# tick-mk-1.net
KiCad netlist of a schematic drawn in EAGLE
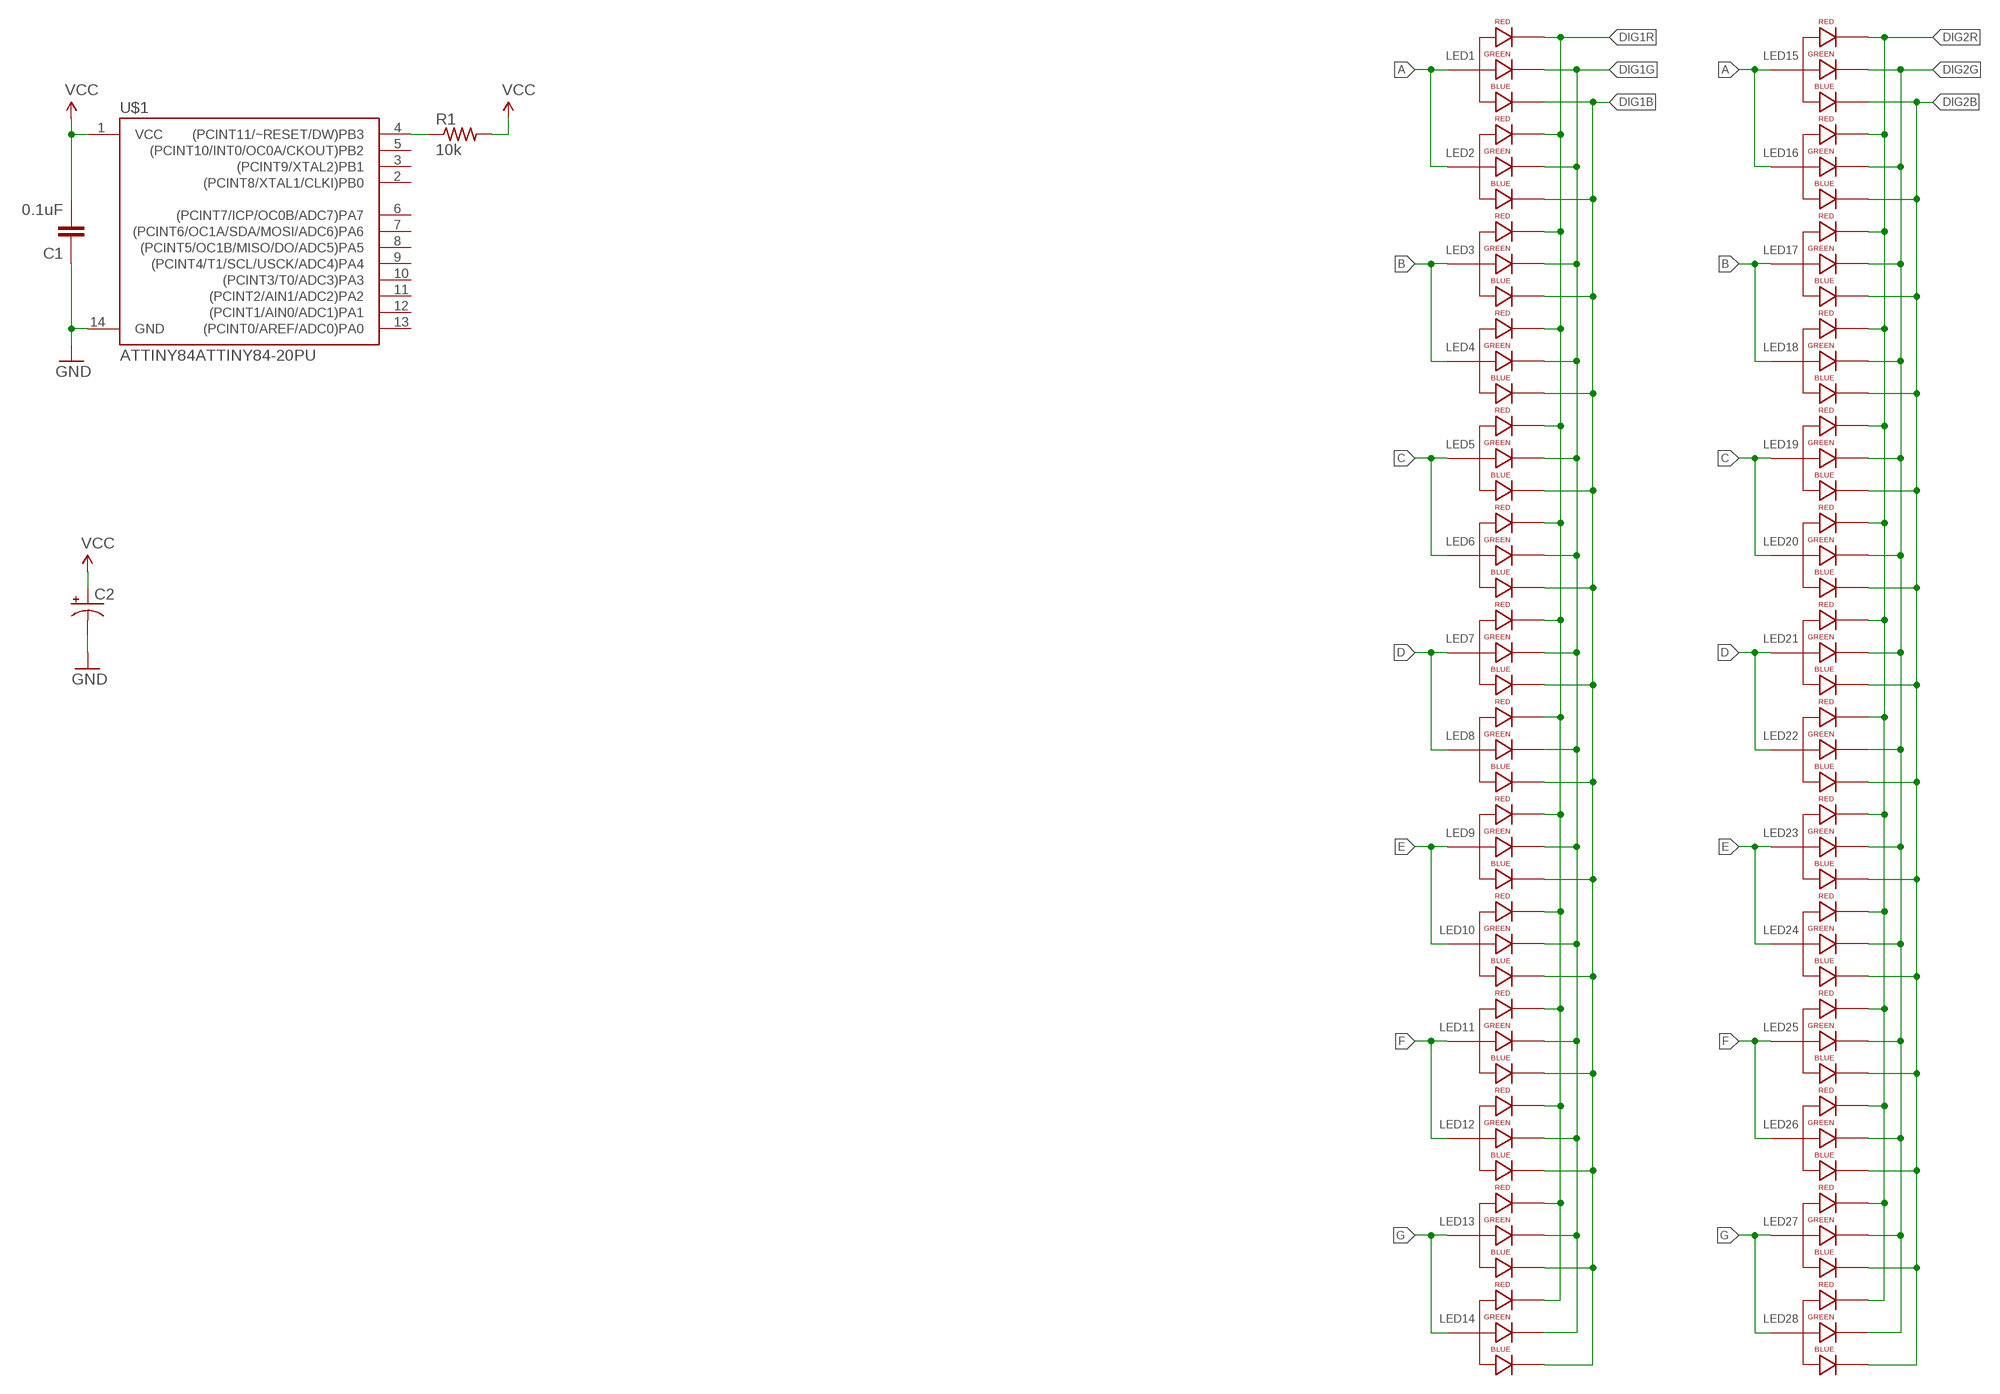
[diagram p0: schematic, sheet 1]

(export (version "E")
  (design (tool "Eeschema 10.0.6"))
  (components
    (comp (ref "C1")
      (value "0.1uF")
      (footprint "eagle-import:C025-024X044")
      (libsource (lib "eagle-import") (part "CAPACITOR-CERAMIC025-024X044"))
    )
    (comp (ref "C2")
      (value "CAPACITOR-POLARIZEDE2-5")
      (footprint "eagle-import:E2-5")
      (libsource (lib "eagle-import") (part "CAPACITOR-POLARIZEDE2-5"))
    )
    (comp (ref "LED1")
      (value "LED-RGB-CA-THRUCLEAR")
      (footprint "eagle-import:LED-RGB-THRU")
      (libsource (lib "eagle-import") (part "LED-RGB-CA-THRUCLEAR"))
    )
    (comp (ref "LED2")
      (value "LED-RGB-CA-THRUCLEAR")
      (footprint "eagle-import:LED-RGB-THRU")
      (libsource (lib "eagle-import") (part "LED-RGB-CA-THRUCLEAR"))
    )
    (comp (ref "LED3")
      (value "LED-RGB-CA-THRUCLEAR")
      (footprint "eagle-import:LED-RGB-THRU")
      (libsource (lib "eagle-import") (part "LED-RGB-CA-THRUCLEAR"))
    )
    (comp (ref "LED4")
      (value "LED-RGB-CA-THRUCLEAR")
      (footprint "eagle-import:LED-RGB-THRU")
      (libsource (lib "eagle-import") (part "LED-RGB-CA-THRUCLEAR"))
    )
    (comp (ref "LED5")
      (value "LED-RGB-CA-THRUCLEAR")
      (footprint "eagle-import:LED-RGB-THRU")
      (libsource (lib "eagle-import") (part "LED-RGB-CA-THRUCLEAR"))
    )
    (comp (ref "LED6")
      (value "LED-RGB-CA-THRUCLEAR")
      (footprint "eagle-import:LED-RGB-THRU")
      (libsource (lib "eagle-import") (part "LED-RGB-CA-THRUCLEAR"))
    )
    (comp (ref "LED7")
      (value "LED-RGB-CA-THRUCLEAR")
      (footprint "eagle-import:LED-RGB-THRU")
      (libsource (lib "eagle-import") (part "LED-RGB-CA-THRUCLEAR"))
    )
    (comp (ref "LED8")
      (value "LED-RGB-CA-THRUCLEAR")
      (footprint "eagle-import:LED-RGB-THRU")
      (libsource (lib "eagle-import") (part "LED-RGB-CA-THRUCLEAR"))
    )
    (comp (ref "LED9")
      (value "LED-RGB-CA-THRUCLEAR")
      (footprint "eagle-import:LED-RGB-THRU")
      (libsource (lib "eagle-import") (part "LED-RGB-CA-THRUCLEAR"))
    )
    (comp (ref "LED10")
      (value "LED-RGB-CA-THRUCLEAR")
      (footprint "eagle-import:LED-RGB-THRU")
      (libsource (lib "eagle-import") (part "LED-RGB-CA-THRUCLEAR"))
    )
    (comp (ref "LED11")
      (value "LED-RGB-CA-THRUCLEAR")
      (footprint "eagle-import:LED-RGB-THRU")
      (libsource (lib "eagle-import") (part "LED-RGB-CA-THRUCLEAR"))
    )
    (comp (ref "LED12")
      (value "LED-RGB-CA-THRUCLEAR")
      (footprint "eagle-import:LED-RGB-THRU")
      (libsource (lib "eagle-import") (part "LED-RGB-CA-THRUCLEAR"))
    )
    (comp (ref "LED13")
      (value "LED-RGB-CA-THRUCLEAR")
      (footprint "eagle-import:LED-RGB-THRU")
      (libsource (lib "eagle-import") (part "LED-RGB-CA-THRUCLEAR"))
    )
    (comp (ref "LED14")
      (value "LED-RGB-CA-THRUCLEAR")
      (footprint "eagle-import:LED-RGB-THRU")
      (libsource (lib "eagle-import") (part "LED-RGB-CA-THRUCLEAR"))
    )
    (comp (ref "LED15")
      (value "LED-RGB-CA-THRUCLEAR")
      (footprint "eagle-import:LED-RGB-THRU")
      (libsource (lib "eagle-import") (part "LED-RGB-CA-THRUCLEAR"))
    )
    (comp (ref "LED16")
      (value "LED-RGB-CA-THRUCLEAR")
      (footprint "eagle-import:LED-RGB-THRU")
      (libsource (lib "eagle-import") (part "LED-RGB-CA-THRUCLEAR"))
    )
    (comp (ref "LED17")
      (value "LED-RGB-CA-THRUCLEAR")
      (footprint "eagle-import:LED-RGB-THRU")
      (libsource (lib "eagle-import") (part "LED-RGB-CA-THRUCLEAR"))
    )
    (comp (ref "LED18")
      (value "LED-RGB-CA-THRUCLEAR")
      (footprint "eagle-import:LED-RGB-THRU")
      (libsource (lib "eagle-import") (part "LED-RGB-CA-THRUCLEAR"))
    )
    (comp (ref "LED19")
      (value "LED-RGB-CA-THRUCLEAR")
      (footprint "eagle-import:LED-RGB-THRU")
      (libsource (lib "eagle-import") (part "LED-RGB-CA-THRUCLEAR"))
    )
    (comp (ref "LED20")
      (value "LED-RGB-CA-THRUCLEAR")
      (footprint "eagle-import:LED-RGB-THRU")
      (libsource (lib "eagle-import") (part "LED-RGB-CA-THRUCLEAR"))
    )
    (comp (ref "LED21")
      (value "LED-RGB-CA-THRUCLEAR")
      (footprint "eagle-import:LED-RGB-THRU")
      (libsource (lib "eagle-import") (part "LED-RGB-CA-THRUCLEAR"))
    )
    (comp (ref "LED22")
      (value "LED-RGB-CA-THRUCLEAR")
      (footprint "eagle-import:LED-RGB-THRU")
      (libsource (lib "eagle-import") (part "LED-RGB-CA-THRUCLEAR"))
    )
    (comp (ref "LED23")
      (value "LED-RGB-CA-THRUCLEAR")
      (footprint "eagle-import:LED-RGB-THRU")
      (libsource (lib "eagle-import") (part "LED-RGB-CA-THRUCLEAR"))
    )
    (comp (ref "LED24")
      (value "LED-RGB-CA-THRUCLEAR")
      (footprint "eagle-import:LED-RGB-THRU")
      (libsource (lib "eagle-import") (part "LED-RGB-CA-THRUCLEAR"))
    )
    (comp (ref "LED25")
      (value "LED-RGB-CA-THRUCLEAR")
      (footprint "eagle-import:LED-RGB-THRU")
      (libsource (lib "eagle-import") (part "LED-RGB-CA-THRUCLEAR"))
    )
    (comp (ref "LED26")
      (value "LED-RGB-CA-THRUCLEAR")
      (footprint "eagle-import:LED-RGB-THRU")
      (libsource (lib "eagle-import") (part "LED-RGB-CA-THRUCLEAR"))
    )
    (comp (ref "LED27")
      (value "LED-RGB-CA-THRUCLEAR")
      (footprint "eagle-import:LED-RGB-THRU")
      (libsource (lib "eagle-import") (part "LED-RGB-CA-THRUCLEAR"))
    )
    (comp (ref "LED28")
      (value "LED-RGB-CA-THRUCLEAR")
      (footprint "eagle-import:LED-RGB-THRU")
      (libsource (lib "eagle-import") (part "LED-RGB-CA-THRUCLEAR"))
    )
    (comp (ref "R1")
      (value "10k")
      (footprint "eagle-import:RESISTOR-AXIAL-PTH-5.08MM")
      (libsource (lib "eagle-import") (part "RESISTORPTH-AXIAL-5.08MM"))
    )
    (comp (ref "U$1")
      (value "ATTINY84ATTINY84-20PU")
      (footprint "eagle-import:DIL14")
      (libsource (lib "eagle-import") (part "ATTINY84ATTINY84-20PU"))
    )
  )
  (nets
    (net (code "1") (name "A") (class "Default")
      (node (ref "LED1") (pin "2") (pinfunction "ANODE_2") (pintype "bidirectional"))
      (node (ref "LED15") (pin "2") (pinfunction "ANODE_2") (pintype "bidirectional"))
      (node (ref "LED16") (pin "2") (pinfunction "ANODE_2") (pintype "bidirectional"))
      (node (ref "LED2") (pin "2") (pinfunction "ANODE_2") (pintype "bidirectional"))
    )
    (net (code "2") (name "B") (class "Default")
      (node (ref "LED17") (pin "2") (pinfunction "ANODE_2") (pintype "bidirectional"))
      (node (ref "LED18") (pin "2") (pinfunction "ANODE_2") (pintype "bidirectional"))
      (node (ref "LED3") (pin "2") (pinfunction "ANODE_2") (pintype "bidirectional"))
      (node (ref "LED4") (pin "2") (pinfunction "ANODE_2") (pintype "bidirectional"))
    )
    (net (code "3") (name "C") (class "Default")
      (node (ref "LED19") (pin "2") (pinfunction "ANODE_2") (pintype "bidirectional"))
      (node (ref "LED20") (pin "2") (pinfunction "ANODE_2") (pintype "bidirectional"))
      (node (ref "LED5") (pin "2") (pinfunction "ANODE_2") (pintype "bidirectional"))
      (node (ref "LED6") (pin "2") (pinfunction "ANODE_2") (pintype "bidirectional"))
    )
    (net (code "4") (name "D") (class "Default")
      (node (ref "LED21") (pin "2") (pinfunction "ANODE_2") (pintype "bidirectional"))
      (node (ref "LED22") (pin "2") (pinfunction "ANODE_2") (pintype "bidirectional"))
      (node (ref "LED7") (pin "2") (pinfunction "ANODE_2") (pintype "bidirectional"))
      (node (ref "LED8") (pin "2") (pinfunction "ANODE_2") (pintype "bidirectional"))
    )
    (net (code "5") (name "DIG1B") (class "Default")
      (node (ref "LED1") (pin "4") (pinfunction "BLUE_CATHODE_4") (pintype "bidirectional"))
      (node (ref "LED10") (pin "4") (pinfunction "BLUE_CATHODE_4") (pintype "bidirectional"))
      (node (ref "LED11") (pin "4") (pinfunction "BLUE_CATHODE_4") (pintype "bidirectional"))
      (node (ref "LED12") (pin "4") (pinfunction "BLUE_CATHODE_4") (pintype "bidirectional"))
      (node (ref "LED13") (pin "4") (pinfunction "BLUE_CATHODE_4") (pintype "bidirectional"))
      (node (ref "LED14") (pin "4") (pinfunction "BLUE_CATHODE_4") (pintype "bidirectional"))
      (node (ref "LED2") (pin "4") (pinfunction "BLUE_CATHODE_4") (pintype "bidirectional"))
      (node (ref "LED3") (pin "4") (pinfunction "BLUE_CATHODE_4") (pintype "bidirectional"))
      (node (ref "LED4") (pin "4") (pinfunction "BLUE_CATHODE_4") (pintype "bidirectional"))
      (node (ref "LED5") (pin "4") (pinfunction "BLUE_CATHODE_4") (pintype "bidirectional"))
      (node (ref "LED6") (pin "4") (pinfunction "BLUE_CATHODE_4") (pintype "bidirectional"))
      (node (ref "LED7") (pin "4") (pinfunction "BLUE_CATHODE_4") (pintype "bidirectional"))
      (node (ref "LED8") (pin "4") (pinfunction "BLUE_CATHODE_4") (pintype "bidirectional"))
      (node (ref "LED9") (pin "4") (pinfunction "BLUE_CATHODE_4") (pintype "bidirectional"))
    )
    (net (code "6") (name "DIG1G") (class "Default")
      (node (ref "LED1") (pin "3") (pinfunction "GREEN_CATHODE_3") (pintype "bidirectional"))
      (node (ref "LED10") (pin "3") (pinfunction "GREEN_CATHODE_3") (pintype "bidirectional"))
      (node (ref "LED11") (pin "3") (pinfunction "GREEN_CATHODE_3") (pintype "bidirectional"))
      (node (ref "LED12") (pin "3") (pinfunction "GREEN_CATHODE_3") (pintype "bidirectional"))
      (node (ref "LED13") (pin "3") (pinfunction "GREEN_CATHODE_3") (pintype "bidirectional"))
      (node (ref "LED14") (pin "3") (pinfunction "GREEN_CATHODE_3") (pintype "bidirectional"))
      (node (ref "LED2") (pin "3") (pinfunction "GREEN_CATHODE_3") (pintype "bidirectional"))
      (node (ref "LED3") (pin "3") (pinfunction "GREEN_CATHODE_3") (pintype "bidirectional"))
      (node (ref "LED4") (pin "3") (pinfunction "GREEN_CATHODE_3") (pintype "bidirectional"))
      (node (ref "LED5") (pin "3") (pinfunction "GREEN_CATHODE_3") (pintype "bidirectional"))
      (node (ref "LED6") (pin "3") (pinfunction "GREEN_CATHODE_3") (pintype "bidirectional"))
      (node (ref "LED7") (pin "3") (pinfunction "GREEN_CATHODE_3") (pintype "bidirectional"))
      (node (ref "LED8") (pin "3") (pinfunction "GREEN_CATHODE_3") (pintype "bidirectional"))
      (node (ref "LED9") (pin "3") (pinfunction "GREEN_CATHODE_3") (pintype "bidirectional"))
    )
    (net (code "7") (name "DIG1R") (class "Default")
      (node (ref "LED1") (pin "1") (pinfunction "RED_CATHODE_1") (pintype "bidirectional"))
      (node (ref "LED10") (pin "1") (pinfunction "RED_CATHODE_1") (pintype "bidirectional"))
      (node (ref "LED11") (pin "1") (pinfunction "RED_CATHODE_1") (pintype "bidirectional"))
      (node (ref "LED12") (pin "1") (pinfunction "RED_CATHODE_1") (pintype "bidirectional"))
      (node (ref "LED13") (pin "1") (pinfunction "RED_CATHODE_1") (pintype "bidirectional"))
      (node (ref "LED14") (pin "1") (pinfunction "RED_CATHODE_1") (pintype "bidirectional"))
      (node (ref "LED2") (pin "1") (pinfunction "RED_CATHODE_1") (pintype "bidirectional"))
      (node (ref "LED3") (pin "1") (pinfunction "RED_CATHODE_1") (pintype "bidirectional"))
      (node (ref "LED4") (pin "1") (pinfunction "RED_CATHODE_1") (pintype "bidirectional"))
      (node (ref "LED5") (pin "1") (pinfunction "RED_CATHODE_1") (pintype "bidirectional"))
      (node (ref "LED6") (pin "1") (pinfunction "RED_CATHODE_1") (pintype "bidirectional"))
      (node (ref "LED7") (pin "1") (pinfunction "RED_CATHODE_1") (pintype "bidirectional"))
      (node (ref "LED8") (pin "1") (pinfunction "RED_CATHODE_1") (pintype "bidirectional"))
      (node (ref "LED9") (pin "1") (pinfunction "RED_CATHODE_1") (pintype "bidirectional"))
    )
    (net (code "8") (name "DIG2B") (class "Default")
      (node (ref "LED15") (pin "4") (pinfunction "BLUE_CATHODE_4") (pintype "bidirectional"))
      (node (ref "LED16") (pin "4") (pinfunction "BLUE_CATHODE_4") (pintype "bidirectional"))
      (node (ref "LED17") (pin "4") (pinfunction "BLUE_CATHODE_4") (pintype "bidirectional"))
      (node (ref "LED18") (pin "4") (pinfunction "BLUE_CATHODE_4") (pintype "bidirectional"))
      (node (ref "LED19") (pin "4") (pinfunction "BLUE_CATHODE_4") (pintype "bidirectional"))
      (node (ref "LED20") (pin "4") (pinfunction "BLUE_CATHODE_4") (pintype "bidirectional"))
      (node (ref "LED21") (pin "4") (pinfunction "BLUE_CATHODE_4") (pintype "bidirectional"))
      (node (ref "LED22") (pin "4") (pinfunction "BLUE_CATHODE_4") (pintype "bidirectional"))
      (node (ref "LED23") (pin "4") (pinfunction "BLUE_CATHODE_4") (pintype "bidirectional"))
      (node (ref "LED24") (pin "4") (pinfunction "BLUE_CATHODE_4") (pintype "bidirectional"))
      (node (ref "LED25") (pin "4") (pinfunction "BLUE_CATHODE_4") (pintype "bidirectional"))
      (node (ref "LED26") (pin "4") (pinfunction "BLUE_CATHODE_4") (pintype "bidirectional"))
      (node (ref "LED27") (pin "4") (pinfunction "BLUE_CATHODE_4") (pintype "bidirectional"))
      (node (ref "LED28") (pin "4") (pinfunction "BLUE_CATHODE_4") (pintype "bidirectional"))
    )
    (net (code "9") (name "DIG2G") (class "Default")
      (node (ref "LED15") (pin "3") (pinfunction "GREEN_CATHODE_3") (pintype "bidirectional"))
      (node (ref "LED16") (pin "3") (pinfunction "GREEN_CATHODE_3") (pintype "bidirectional"))
      (node (ref "LED17") (pin "3") (pinfunction "GREEN_CATHODE_3") (pintype "bidirectional"))
      (node (ref "LED18") (pin "3") (pinfunction "GREEN_CATHODE_3") (pintype "bidirectional"))
      (node (ref "LED19") (pin "3") (pinfunction "GREEN_CATHODE_3") (pintype "bidirectional"))
      (node (ref "LED20") (pin "3") (pinfunction "GREEN_CATHODE_3") (pintype "bidirectional"))
      (node (ref "LED21") (pin "3") (pinfunction "GREEN_CATHODE_3") (pintype "bidirectional"))
      (node (ref "LED22") (pin "3") (pinfunction "GREEN_CATHODE_3") (pintype "bidirectional"))
      (node (ref "LED23") (pin "3") (pinfunction "GREEN_CATHODE_3") (pintype "bidirectional"))
      (node (ref "LED24") (pin "3") (pinfunction "GREEN_CATHODE_3") (pintype "bidirectional"))
      (node (ref "LED25") (pin "3") (pinfunction "GREEN_CATHODE_3") (pintype "bidirectional"))
      (node (ref "LED26") (pin "3") (pinfunction "GREEN_CATHODE_3") (pintype "bidirectional"))
      (node (ref "LED27") (pin "3") (pinfunction "GREEN_CATHODE_3") (pintype "bidirectional"))
      (node (ref "LED28") (pin "3") (pinfunction "GREEN_CATHODE_3") (pintype "bidirectional"))
    )
    (net (code "10") (name "DIG2R") (class "Default")
      (node (ref "LED15") (pin "1") (pinfunction "RED_CATHODE_1") (pintype "bidirectional"))
      (node (ref "LED16") (pin "1") (pinfunction "RED_CATHODE_1") (pintype "bidirectional"))
      (node (ref "LED17") (pin "1") (pinfunction "RED_CATHODE_1") (pintype "bidirectional"))
      (node (ref "LED18") (pin "1") (pinfunction "RED_CATHODE_1") (pintype "bidirectional"))
      (node (ref "LED19") (pin "1") (pinfunction "RED_CATHODE_1") (pintype "bidirectional"))
      (node (ref "LED20") (pin "1") (pinfunction "RED_CATHODE_1") (pintype "bidirectional"))
      (node (ref "LED21") (pin "1") (pinfunction "RED_CATHODE_1") (pintype "bidirectional"))
      (node (ref "LED22") (pin "1") (pinfunction "RED_CATHODE_1") (pintype "bidirectional"))
      (node (ref "LED23") (pin "1") (pinfunction "RED_CATHODE_1") (pintype "bidirectional"))
      (node (ref "LED24") (pin "1") (pinfunction "RED_CATHODE_1") (pintype "bidirectional"))
      (node (ref "LED25") (pin "1") (pinfunction "RED_CATHODE_1") (pintype "bidirectional"))
      (node (ref "LED26") (pin "1") (pinfunction "RED_CATHODE_1") (pintype "bidirectional"))
      (node (ref "LED27") (pin "1") (pinfunction "RED_CATHODE_1") (pintype "bidirectional"))
      (node (ref "LED28") (pin "1") (pinfunction "RED_CATHODE_1") (pintype "bidirectional"))
    )
    (net (code "11") (name "E") (class "Default")
      (node (ref "LED10") (pin "2") (pinfunction "ANODE_2") (pintype "bidirectional"))
      (node (ref "LED23") (pin "2") (pinfunction "ANODE_2") (pintype "bidirectional"))
      (node (ref "LED24") (pin "2") (pinfunction "ANODE_2") (pintype "bidirectional"))
      (node (ref "LED9") (pin "2") (pinfunction "ANODE_2") (pintype "bidirectional"))
    )
    (net (code "12") (name "F") (class "Default")
      (node (ref "LED11") (pin "2") (pinfunction "ANODE_2") (pintype "bidirectional"))
      (node (ref "LED12") (pin "2") (pinfunction "ANODE_2") (pintype "bidirectional"))
      (node (ref "LED25") (pin "2") (pinfunction "ANODE_2") (pintype "bidirectional"))
      (node (ref "LED26") (pin "2") (pinfunction "ANODE_2") (pintype "bidirectional"))
    )
    (net (code "13") (name "G") (class "Default")
      (node (ref "LED13") (pin "2") (pinfunction "ANODE_2") (pintype "bidirectional"))
      (node (ref "LED14") (pin "2") (pinfunction "ANODE_2") (pintype "bidirectional"))
      (node (ref "LED27") (pin "2") (pinfunction "ANODE_2") (pintype "bidirectional"))
      (node (ref "LED28") (pin "2") (pinfunction "ANODE_2") (pintype "bidirectional"))
    )
    (net (code "14") (name "GND") (class "Default")
      (node (ref "C1") (pin "1") (pinfunction "1_1") (pintype "passive"))
      (node (ref "C2") (pin "-") (pinfunction "-_-") (pintype "passive"))
      (node (ref "U$1") (pin "14") (pinfunction "GND_14") (pintype "bidirectional"))
    )
    (net (code "15") (name "Net-(R1-1)") (class "Default")
      (node (ref "R1") (pin "P$1") (pinfunction "1_P$1") (pintype "passive"))
      (node (ref "U$1") (pin "4") (pinfunction "(PCINT11/~{RESET/DW})PB3_4") (pintype "bidirectional"))
    )
    (net (code "16") (name "VCC") (class "Default")
      (node (ref "C1") (pin "2") (pinfunction "2_2") (pintype "passive"))
      (node (ref "C2") (pin "+") (pinfunction "+_+") (pintype "passive"))
      (node (ref "R1") (pin "P$2") (pinfunction "2_P$2") (pintype "passive"))
      (node (ref "U$1") (pin "1") (pinfunction "VCC_1") (pintype "bidirectional"))
    )
    (net (code "17") (name "unconnected-(U$1-(PCINT0{slash}AREF{slash}ADC0)PA0-Pad13)") (class "Default")
      (node (ref "U$1") (pin "13") (pinfunction "(PCINT0/AREF/ADC0)PA0_13") (pintype "bidirectional"))
    )
    (net (code "18") (name "unconnected-(U$1-(PCINT1{slash}AIN0{slash}ADC1)PA1-Pad12)") (class "Default")
      (node (ref "U$1") (pin "12") (pinfunction "(PCINT1/AIN0/ADC1)PA1_12") (pintype "bidirectional"))
    )
    (net (code "19") (name "unconnected-(U$1-(PCINT2{slash}AIN1{slash}ADC2)PA2-Pad11)") (class "Default")
      (node (ref "U$1") (pin "11") (pinfunction "(PCINT2/AIN1/ADC2)PA2_11") (pintype "bidirectional"))
    )
    (net (code "20") (name "unconnected-(U$1-(PCINT3{slash}T0{slash}ADC3)PA3-Pad10)") (class "Default")
      (node (ref "U$1") (pin "10") (pinfunction "(PCINT3/T0/ADC3)PA3_10") (pintype "bidirectional"))
    )
    (net (code "21") (name "unconnected-(U$1-(PCINT4{slash}T1{slash}SCL{slash}USCK{slash}ADC4)PA4-Pad9)") (class "Default")
      (node (ref "U$1") (pin "9") (pinfunction "(PCINT4/T1/SCL/USCK/ADC4)PA4_9") (pintype "bidirectional"))
    )
    (net (code "22") (name "unconnected-(U$1-(PCINT5{slash}OC1B{slash}MISO{slash}DO{slash}ADC5)PA5-Pad8)") (class "Default")
      (node (ref "U$1") (pin "8") (pinfunction "(PCINT5/OC1B/MISO/DO/ADC5)PA5_8") (pintype "bidirectional"))
    )
    (net (code "23") (name "unconnected-(U$1-(PCINT6{slash}OC1A{slash}SDA{slash}MOSI{slash}ADC6)PA6-Pad7)") (class "Default")
      (node (ref "U$1") (pin "7") (pinfunction "(PCINT6/OC1A/SDA/MOSI/ADC6)PA6_7") (pintype "bidirectional"))
    )
    (net (code "24") (name "unconnected-(U$1-(PCINT7{slash}ICP{slash}OC0B{slash}ADC7)PA7-Pad6)") (class "Default")
      (node (ref "U$1") (pin "6") (pinfunction "(PCINT7/ICP/OC0B/ADC7)PA7_6") (pintype "bidirectional"))
    )
    (net (code "25") (name "unconnected-(U$1-(PCINT8{slash}XTAL1{slash}CLKI)PB0-Pad2)") (class "Default")
      (node (ref "U$1") (pin "2") (pinfunction "(PCINT8/XTAL1/CLKI)PB0_2") (pintype "bidirectional"))
    )
    (net (code "26") (name "unconnected-(U$1-(PCINT9{slash}XTAL2)PB1-Pad3)") (class "Default")
      (node (ref "U$1") (pin "3") (pinfunction "(PCINT9/XTAL2)PB1_3") (pintype "bidirectional"))
    )
    (net (code "27") (name "unconnected-(U$1-(PCINT10{slash}INT0{slash}OC0A{slash}CKOUT)PB2-Pad5)") (class "Default")
      (node (ref "U$1") (pin "5") (pinfunction "(PCINT10/INT0/OC0A/CKOUT)PB2_5") (pintype "bidirectional"))
    )
  )
)
